# booz_imu_v.net
KiCad netlist of a schematic drawn in EAGLE
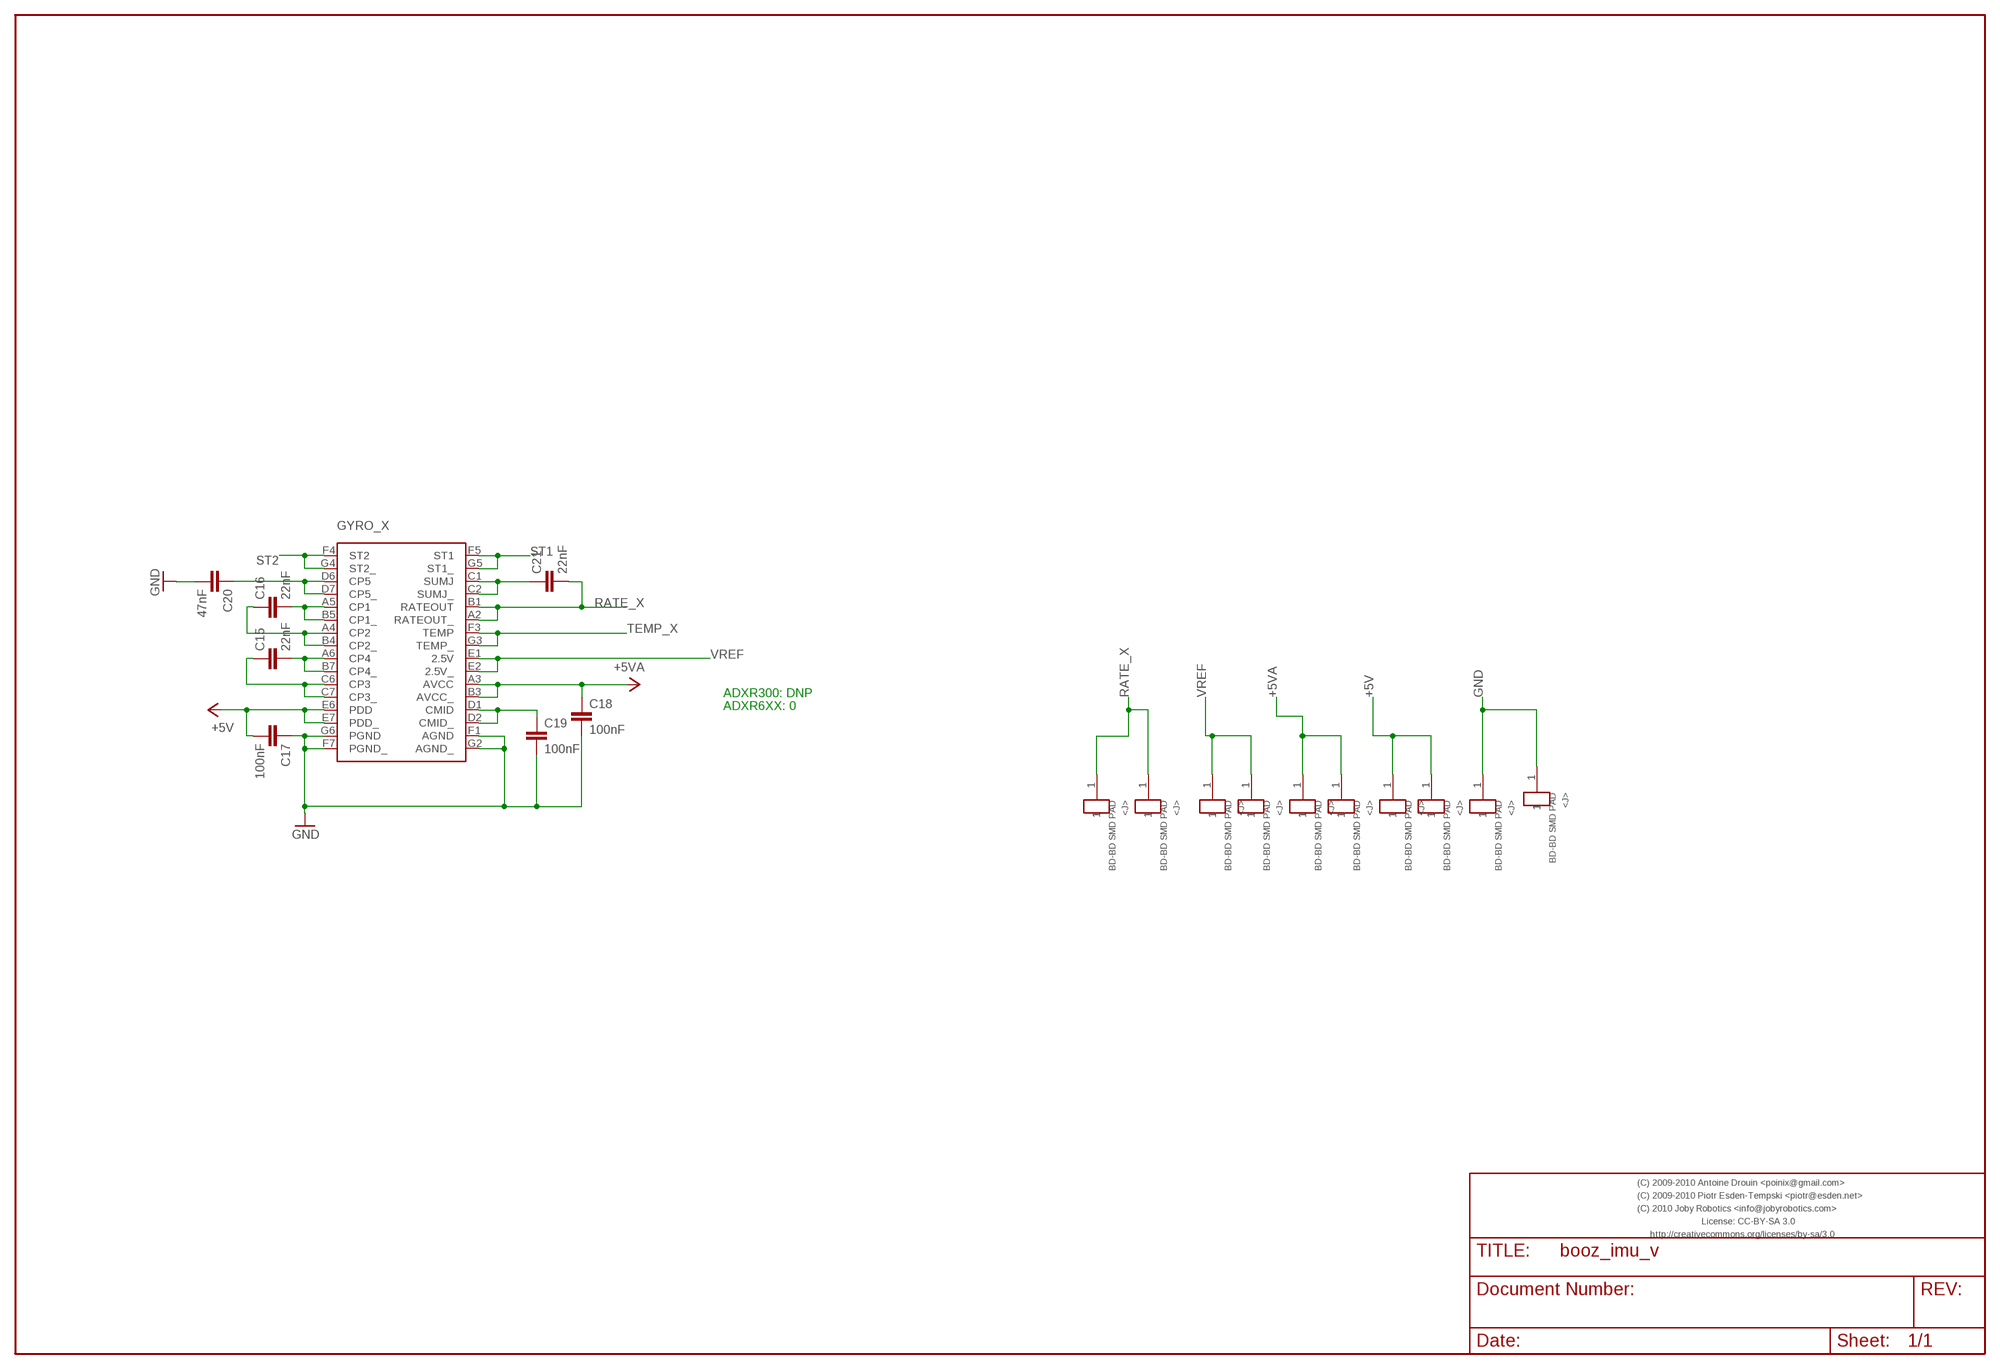
[diagram p0: schematic, sheet 1]

(export (version "E")
  (design (tool "Eeschema 10.0.6"))
  (components
    (comp (ref "C15")
      (value "22nF")
      (footprint "eagle-import:0603-CAP")
      (libsource (lib "eagle-import") (part "CAPACITOR-0603"))
    )
    (comp (ref "C16")
      (value "22nF")
      (footprint "eagle-import:0603-CAP")
      (libsource (lib "eagle-import") (part "CAPACITOR-0603"))
    )
    (comp (ref "C17")
      (value "100nF")
      (footprint "eagle-import:0603-CAP")
      (libsource (lib "eagle-import") (part "CAPACITOR-0603"))
    )
    (comp (ref "C18")
      (value "100nF")
      (footprint "eagle-import:0603-CAP")
      (libsource (lib "eagle-import") (part "CAPACITOR-0603"))
    )
    (comp (ref "C19")
      (value "100nF")
      (footprint "eagle-import:0603-CAP")
      (libsource (lib "eagle-import") (part "CAPACITOR-0603"))
    )
    (comp (ref "C20")
      (value "47nF")
      (footprint "eagle-import:0603-CAP")
      (libsource (lib "eagle-import") (part "CAPACITOR-0603"))
    )
    (comp (ref "C21")
      (value "22nF")
      (footprint "eagle-import:0603-CAP")
      (libsource (lib "eagle-import") (part "CAPACITOR-0603"))
    )
    (comp (ref "GYRO_X")
      (value "ADXR")
      (footprint "eagle-import:BC-32")
      (libsource (lib "eagle-import") (part "ADXR"))
    )
    (comp (ref "J1")
      (value "SOLDERPAD25X160")
      (footprint "eagle-import:SOLDERPAD25X160")
      (libsource (lib "eagle-import") (part "SOLDERPAD25X160"))
    )
    (comp (ref "J2")
      (value "SOLDERPAD25X160")
      (footprint "eagle-import:SOLDERPAD25X160")
      (libsource (lib "eagle-import") (part "SOLDERPAD25X160"))
    )
    (comp (ref "J3")
      (value "SOLDERPAD25X160")
      (footprint "eagle-import:SOLDERPAD25X160")
      (libsource (lib "eagle-import") (part "SOLDERPAD25X160"))
    )
    (comp (ref "J4")
      (value "SOLDERPAD25X160")
      (footprint "eagle-import:SOLDERPAD25X160")
      (libsource (lib "eagle-import") (part "SOLDERPAD25X160"))
    )
    (comp (ref "J5")
      (value "SOLDERPAD25X160")
      (footprint "eagle-import:SOLDERPAD25X160")
      (libsource (lib "eagle-import") (part "SOLDERPAD25X160"))
    )
    (comp (ref "J6")
      (value "SOLDERPAD25X160")
      (footprint "eagle-import:SOLDERPAD25X160")
      (libsource (lib "eagle-import") (part "SOLDERPAD25X160"))
    )
    (comp (ref "J7")
      (value "SOLDERPAD25X160")
      (footprint "eagle-import:SOLDERPAD25X160")
      (libsource (lib "eagle-import") (part "SOLDERPAD25X160"))
    )
    (comp (ref "J8")
      (value "SOLDERPAD25X160")
      (footprint "eagle-import:SOLDERPAD25X160")
      (libsource (lib "eagle-import") (part "SOLDERPAD25X160"))
    )
    (comp (ref "J9")
      (value "SOLDERPAD25X160")
      (footprint "eagle-import:SOLDERPAD25X160")
      (libsource (lib "eagle-import") (part "SOLDERPAD25X160"))
    )
    (comp (ref "J10")
      (value "SOLDERPAD25X160")
      (footprint "eagle-import:SOLDERPAD25X160")
      (libsource (lib "eagle-import") (part "SOLDERPAD25X160"))
    )
  )
  (nets
    (net (code "1") (name "+5V") (class "Default")
      (node (ref "C17") (pin "P$2") (pinfunction "2_P$2") (pintype "passive"))
      (node (ref "GYRO_X") (pin "E6") (pinfunction "PDD_E6") (pintype "bidirectional"))
      (node (ref "GYRO_X") (pin "E7") (pinfunction "PDD__E7") (pintype "bidirectional"))
      (node (ref "J8") (pin "1") (pinfunction "1_1") (pintype "bidirectional"))
      (node (ref "J9") (pin "1") (pinfunction "1_1") (pintype "bidirectional"))
    )
    (net (code "2") (name "+5VA") (class "Default")
      (node (ref "C18") (pin "P$1") (pinfunction "1_P$1") (pintype "passive"))
      (node (ref "GYRO_X") (pin "A3") (pinfunction "AVCC_A3") (pintype "bidirectional"))
      (node (ref "GYRO_X") (pin "B3") (pinfunction "AVCC__B3") (pintype "bidirectional"))
      (node (ref "J6") (pin "1") (pinfunction "1_1") (pintype "bidirectional"))
      (node (ref "J7") (pin "1") (pinfunction "1_1") (pintype "bidirectional"))
    )
    (net (code "3") (name "/RATE_X") (class "Default")
      (node (ref "C21") (pin "P$2") (pinfunction "2_P$2") (pintype "passive"))
      (node (ref "GYRO_X") (pin "A2") (pinfunction "RATEOUT__A2") (pintype "bidirectional"))
      (node (ref "GYRO_X") (pin "B1") (pinfunction "RATEOUT_B1") (pintype "bidirectional"))
      (node (ref "J1") (pin "1") (pinfunction "1_1") (pintype "bidirectional"))
      (node (ref "J3") (pin "1") (pinfunction "1_1") (pintype "bidirectional"))
    )
    (net (code "4") (name "/ST1") (class "Default")
      (node (ref "GYRO_X") (pin "F5") (pinfunction "ST1_F5") (pintype "bidirectional"))
      (node (ref "GYRO_X") (pin "G5") (pinfunction "ST1__G5") (pintype "bidirectional"))
    )
    (net (code "5") (name "/ST2") (class "Default")
      (node (ref "GYRO_X") (pin "F4") (pinfunction "ST2_F4") (pintype "bidirectional"))
      (node (ref "GYRO_X") (pin "G4") (pinfunction "ST2__G4") (pintype "bidirectional"))
    )
    (net (code "6") (name "/TEMP_X") (class "Default")
      (node (ref "GYRO_X") (pin "F3") (pinfunction "TEMP_F3") (pintype "bidirectional"))
      (node (ref "GYRO_X") (pin "G3") (pinfunction "TEMP__G3") (pintype "bidirectional"))
    )
    (net (code "7") (name "/VREF") (class "Default")
      (node (ref "GYRO_X") (pin "E1") (pinfunction "2.5V_E1") (pintype "bidirectional"))
      (node (ref "GYRO_X") (pin "E2") (pinfunction "2.5V__E2") (pintype "bidirectional"))
      (node (ref "J4") (pin "1") (pinfunction "1_1") (pintype "bidirectional"))
      (node (ref "J5") (pin "1") (pinfunction "1_1") (pintype "bidirectional"))
    )
    (net (code "8") (name "GND") (class "Default")
      (node (ref "C17") (pin "P$1") (pinfunction "1_P$1") (pintype "passive"))
      (node (ref "C18") (pin "P$2") (pinfunction "2_P$2") (pintype "passive"))
      (node (ref "C19") (pin "P$2") (pinfunction "2_P$2") (pintype "passive"))
      (node (ref "C20") (pin "P$2") (pinfunction "2_P$2") (pintype "passive"))
      (node (ref "GYRO_X") (pin "F1") (pinfunction "AGND_F1") (pintype "bidirectional"))
      (node (ref "GYRO_X") (pin "F7") (pinfunction "PGND__F7") (pintype "bidirectional"))
      (node (ref "GYRO_X") (pin "G2") (pinfunction "AGND__G2") (pintype "bidirectional"))
      (node (ref "GYRO_X") (pin "G6") (pinfunction "PGND_G6") (pintype "bidirectional"))
      (node (ref "J10") (pin "1") (pinfunction "1_1") (pintype "bidirectional"))
      (node (ref "J2") (pin "1") (pinfunction "1_1") (pintype "bidirectional"))
    )
    (net (code "9") (name "Net-(C15-1)") (class "Default")
      (node (ref "C15") (pin "P$1") (pinfunction "1_P$1") (pintype "passive"))
      (node (ref "GYRO_X") (pin "C6") (pinfunction "CP3_C6") (pintype "bidirectional"))
      (node (ref "GYRO_X") (pin "C7") (pinfunction "CP3__C7") (pintype "bidirectional"))
    )
    (net (code "10") (name "Net-(C15-2)") (class "Default")
      (node (ref "C15") (pin "P$2") (pinfunction "2_P$2") (pintype "passive"))
      (node (ref "GYRO_X") (pin "A6") (pinfunction "CP4_A6") (pintype "bidirectional"))
      (node (ref "GYRO_X") (pin "B7") (pinfunction "CP4__B7") (pintype "bidirectional"))
    )
    (net (code "11") (name "Net-(C16-1)") (class "Default")
      (node (ref "C16") (pin "P$1") (pinfunction "1_P$1") (pintype "passive"))
      (node (ref "GYRO_X") (pin "A4") (pinfunction "CP2_A4") (pintype "bidirectional"))
      (node (ref "GYRO_X") (pin "B4") (pinfunction "CP2__B4") (pintype "bidirectional"))
    )
    (net (code "12") (name "Net-(C16-2)") (class "Default")
      (node (ref "C16") (pin "P$2") (pinfunction "2_P$2") (pintype "passive"))
      (node (ref "GYRO_X") (pin "A5") (pinfunction "CP1_A5") (pintype "bidirectional"))
      (node (ref "GYRO_X") (pin "B5") (pinfunction "CP1__B5") (pintype "bidirectional"))
    )
    (net (code "13") (name "Net-(C19-1)") (class "Default")
      (node (ref "C19") (pin "P$1") (pinfunction "1_P$1") (pintype "passive"))
      (node (ref "GYRO_X") (pin "D1") (pinfunction "CMID_D1") (pintype "bidirectional"))
      (node (ref "GYRO_X") (pin "D2") (pinfunction "CMID__D2") (pintype "bidirectional"))
    )
    (net (code "14") (name "Net-(C20-1)") (class "Default")
      (node (ref "C20") (pin "P$1") (pinfunction "1_P$1") (pintype "passive"))
      (node (ref "GYRO_X") (pin "D6") (pinfunction "CP5_D6") (pintype "bidirectional"))
      (node (ref "GYRO_X") (pin "D7") (pinfunction "CP5__D7") (pintype "bidirectional"))
    )
    (net (code "15") (name "Net-(C21-1)") (class "Default")
      (node (ref "C21") (pin "P$1") (pinfunction "1_P$1") (pintype "passive"))
      (node (ref "GYRO_X") (pin "C1") (pinfunction "SUMJ_C1") (pintype "bidirectional"))
      (node (ref "GYRO_X") (pin "C2") (pinfunction "SUMJ__C2") (pintype "bidirectional"))
    )
  )
)
